# duplikasi_PCB.net
KiCad netlist of a schematic drawn in EAGLE
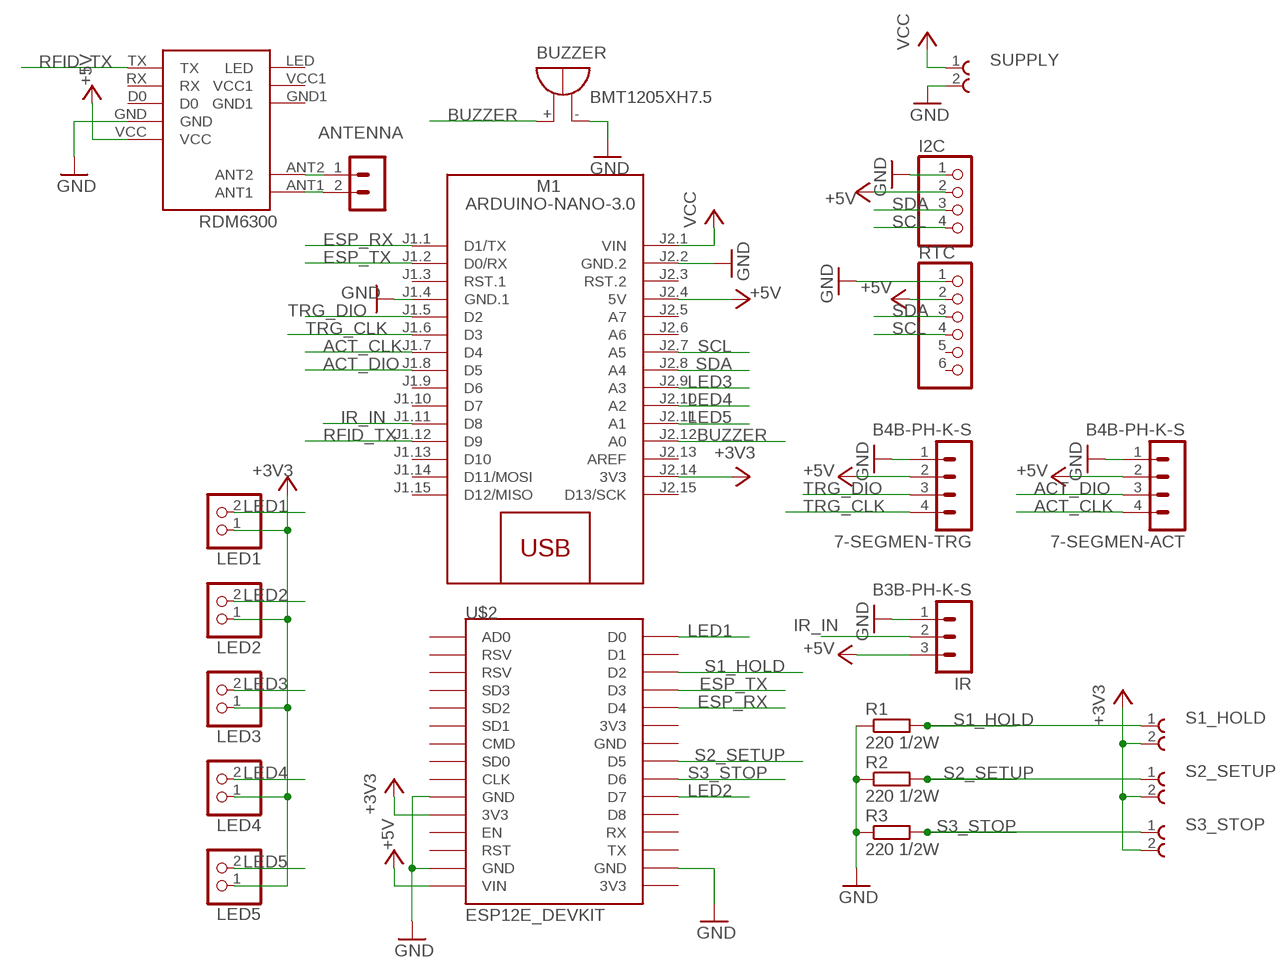
[diagram p0: schematic, sheet 1]

(export (version "E")
  (design (tool "Eeschema 10.0.6"))
  (components
    (comp (ref "7-SEGMEN-ACT")
      (value "B4B-PH-K-S")
      (footprint "eagle-import:B4B-PH-K-S")
      (libsource (lib "eagle-import") (part "B4B-PH-K-S"))
    )
    (comp (ref "7-SEGMEN-TRG")
      (value "B4B-PH-K-S")
      (footprint "eagle-import:B4B-PH-K-S")
      (libsource (lib "eagle-import") (part "B4B-PH-K-S"))
    )
    (comp (ref "ANTENNA")
      (value "B2B-PH-K-S")
      (footprint "eagle-import:B2B-PH-K-S")
      (libsource (lib "eagle-import") (part "B2B-PH-K-S"))
    )
    (comp (ref "BUZZER")
      (value "BMT1205XH7.5")
      (footprint "eagle-import:BMT1205XH7.5")
      (libsource (lib "eagle-import") (part "BMT1205XH7.5"))
    )
    (comp (ref "I2C")
      (value "PINHD-1X4")
      (footprint "eagle-import:1X04")
      (libsource (lib "eagle-import") (part "PINHD-1X4"))
    )
    (comp (ref "IR")
      (value "B3B-PH-K-S")
      (footprint "eagle-import:B3B-PH-K-S")
      (libsource (lib "eagle-import") (part "B3B-PH-K-S"))
    )
    (comp (ref "LED1")
      (value "PINHD-1X2")
      (footprint "eagle-import:1X02")
      (libsource (lib "eagle-import") (part "PINHD-1X2"))
    )
    (comp (ref "LED2")
      (value "PINHD-1X2")
      (footprint "eagle-import:1X02")
      (libsource (lib "eagle-import") (part "PINHD-1X2"))
    )
    (comp (ref "LED3")
      (value "PINHD-1X2")
      (footprint "eagle-import:1X02")
      (libsource (lib "eagle-import") (part "PINHD-1X2"))
    )
    (comp (ref "LED4")
      (value "PINHD-1X2")
      (footprint "eagle-import:1X02")
      (libsource (lib "eagle-import") (part "PINHD-1X2"))
    )
    (comp (ref "LED5")
      (value "PINHD-1X2")
      (footprint "eagle-import:1X02")
      (libsource (lib "eagle-import") (part "PINHD-1X2"))
    )
    (comp (ref "M1")
      (value "ARDUINO-NANO-3.0")
      (footprint "eagle-import:ARDUINO-NANO-3.0")
      (libsource (lib "eagle-import") (part "ARDUINO-NANO-3.0"))
    )
    (comp (ref "R1")
      (value "220 1/2W")
      (footprint "eagle-import:0207_10")
      (libsource (lib "eagle-import") (part "R-EU_0207/10"))
    )
    (comp (ref "R2")
      (value "220 1/2W")
      (footprint "eagle-import:0207_10")
      (libsource (lib "eagle-import") (part "R-EU_0207/10"))
    )
    (comp (ref "R3")
      (value "220 1/2W")
      (footprint "eagle-import:0207_10")
      (libsource (lib "eagle-import") (part "R-EU_0207/10"))
    )
    (comp (ref "RDM1")
      (value "RDM6300")
      (footprint "eagle-import:RDM6300")
      (libsource (lib "eagle-import") (part "RDM6300"))
    )
    (comp (ref "RTC")
      (value "PINHD-1X6")
      (footprint "eagle-import:1X06")
      (libsource (lib "eagle-import") (part "PINHD-1X6"))
    )
    (comp (ref "S1_HOLD")
      (value "691101710002")
      (footprint "eagle-import:691101710002")
      (libsource (lib "eagle-import") (part "691101710002"))
    )
    (comp (ref "S2_SETUP")
      (value "691101710002")
      (footprint "eagle-import:691101710002")
      (libsource (lib "eagle-import") (part "691101710002"))
    )
    (comp (ref "S3_STOP")
      (value "691101710002")
      (footprint "eagle-import:691101710002")
      (libsource (lib "eagle-import") (part "691101710002"))
    )
    (comp (ref "SUPPLY")
      (value "691101710002")
      (footprint "eagle-import:691101710002")
      (libsource (lib "eagle-import") (part "691101710002"))
    )
    (comp (ref "U$2")
      (value "ESP12E_DEVKIT")
      (footprint "eagle-import:ESP12E_DEVKIT")
      (libsource (lib "eagle-import") (part "ESP12E_DEVKIT"))
    )
  )
  (nets
    (net (code "1") (name "+3V3") (class "Default")
      (node (ref "LED1") (pin "1") (pinfunction "1_1") (pintype "passive"))
      (node (ref "LED2") (pin "1") (pinfunction "1_1") (pintype "passive"))
      (node (ref "LED3") (pin "1") (pinfunction "1_1") (pintype "passive"))
      (node (ref "LED4") (pin "1") (pinfunction "1_1") (pintype "passive"))
      (node (ref "LED5") (pin "1") (pinfunction "1_1") (pintype "passive"))
      (node (ref "M1") (pin "J2.14") (pinfunction "3V3_J2.14") (pintype "power_in"))
      (node (ref "S1_HOLD") (pin "2") (pinfunction "2_2") (pintype "passive"))
      (node (ref "S2_SETUP") (pin "2") (pinfunction "2_2") (pintype "passive"))
      (node (ref "S3_STOP") (pin "2") (pinfunction "2_2") (pintype "passive"))
      (node (ref "U$2") (pin "3V3@0") (pinfunction "3V3_3V3@0") (pintype "bidirectional"))
    )
    (net (code "2") (name "+5V") (class "Default")
      (node (ref "7-SEGMEN-ACT") (pin "2") (pinfunction "2_2") (pintype "passive"))
      (node (ref "7-SEGMEN-TRG") (pin "2") (pinfunction "2_2") (pintype "passive"))
      (node (ref "I2C") (pin "2") (pinfunction "2_2") (pintype "passive"))
      (node (ref "IR") (pin "3") (pinfunction "3_3") (pintype "passive"))
      (node (ref "M1") (pin "J2.4") (pinfunction "5V_J2.4") (pintype "power_in"))
      (node (ref "RDM1") (pin "VCC") (pinfunction "VCC_VCC") (pintype "bidirectional"))
      (node (ref "RTC") (pin "2") (pinfunction "2_2") (pintype "passive"))
      (node (ref "U$2") (pin "VIN") (pinfunction "VIN_VIN") (pintype "bidirectional"))
    )
    (net (code "3") (name "/ACT_CLK") (class "Default")
      (node (ref "7-SEGMEN-ACT") (pin "4") (pinfunction "4_4") (pintype "passive"))
      (node (ref "M1") (pin "J1.7") (pinfunction "D4_J1.7") (pintype "bidirectional"))
    )
    (net (code "4") (name "/ACT_DIO") (class "Default")
      (node (ref "7-SEGMEN-ACT") (pin "3") (pinfunction "3_3") (pintype "passive"))
      (node (ref "M1") (pin "J1.8") (pinfunction "D5_J1.8") (pintype "bidirectional"))
    )
    (net (code "5") (name "/BUZZER") (class "Default")
      (node (ref "BUZZER") (pin "+") (pinfunction "+_+") (pintype "passive"))
      (node (ref "M1") (pin "J2.12") (pinfunction "A0_J2.12") (pintype "bidirectional"))
    )
    (net (code "6") (name "/ESP_RX") (class "Default")
      (node (ref "M1") (pin "J1.1") (pinfunction "D1/TX_J1.1") (pintype "bidirectional"))
      (node (ref "U$2") (pin "D4") (pinfunction "D4_D4") (pintype "bidirectional"))
    )
    (net (code "7") (name "/ESP_TX") (class "Default")
      (node (ref "M1") (pin "J1.2") (pinfunction "D0/RX_J1.2") (pintype "bidirectional"))
      (node (ref "U$2") (pin "D3") (pinfunction "D3_D3") (pintype "bidirectional"))
    )
    (net (code "8") (name "/IR_IN") (class "Default")
      (node (ref "IR") (pin "2") (pinfunction "2_2") (pintype "passive"))
      (node (ref "M1") (pin "J1.11") (pinfunction "D8_J1.11") (pintype "bidirectional"))
    )
    (net (code "9") (name "/LED1") (class "Default")
      (node (ref "LED1") (pin "2") (pinfunction "2_2") (pintype "passive"))
      (node (ref "U$2") (pin "D0") (pinfunction "D0_D0") (pintype "bidirectional"))
    )
    (net (code "10") (name "/LED2") (class "Default")
      (node (ref "LED2") (pin "2") (pinfunction "2_2") (pintype "passive"))
      (node (ref "U$2") (pin "D7") (pinfunction "D7_D7") (pintype "bidirectional"))
    )
    (net (code "11") (name "/LED3") (class "Default")
      (node (ref "LED3") (pin "2") (pinfunction "2_2") (pintype "passive"))
      (node (ref "M1") (pin "J2.9") (pinfunction "A3_J2.9") (pintype "bidirectional"))
    )
    (net (code "12") (name "/LED4") (class "Default")
      (node (ref "LED4") (pin "2") (pinfunction "2_2") (pintype "passive"))
      (node (ref "M1") (pin "J2.10") (pinfunction "A2_J2.10") (pintype "bidirectional"))
    )
    (net (code "13") (name "/LED5") (class "Default")
      (node (ref "LED5") (pin "2") (pinfunction "2_2") (pintype "passive"))
      (node (ref "M1") (pin "J2.11") (pinfunction "A1_J2.11") (pintype "bidirectional"))
    )
    (net (code "14") (name "/RFID_TX") (class "Default")
      (node (ref "M1") (pin "J1.12") (pinfunction "D9_J1.12") (pintype "bidirectional"))
      (node (ref "RDM1") (pin "TX") (pinfunction "TX_TX") (pintype "bidirectional"))
    )
    (net (code "15") (name "/S1_HOLD") (class "Default")
      (node (ref "R1") (pin "2") (pinfunction "2_2") (pintype "passive"))
      (node (ref "S1_HOLD") (pin "1") (pinfunction "1_1") (pintype "passive"))
      (node (ref "U$2") (pin "D2") (pinfunction "D2_D2") (pintype "bidirectional"))
    )
    (net (code "16") (name "/S2_SETUP") (class "Default")
      (node (ref "R2") (pin "2") (pinfunction "2_2") (pintype "passive"))
      (node (ref "S2_SETUP") (pin "1") (pinfunction "1_1") (pintype "passive"))
      (node (ref "U$2") (pin "D5") (pinfunction "D5_D5") (pintype "bidirectional"))
    )
    (net (code "17") (name "/S3_STOP") (class "Default")
      (node (ref "R3") (pin "2") (pinfunction "2_2") (pintype "passive"))
      (node (ref "S3_STOP") (pin "1") (pinfunction "1_1") (pintype "passive"))
      (node (ref "U$2") (pin "D6") (pinfunction "D6_D6") (pintype "bidirectional"))
    )
    (net (code "18") (name "/SCL") (class "Default")
      (node (ref "I2C") (pin "4") (pinfunction "4_4") (pintype "passive"))
      (node (ref "M1") (pin "J2.7") (pinfunction "A5_J2.7") (pintype "bidirectional"))
      (node (ref "RTC") (pin "4") (pinfunction "4_4") (pintype "passive"))
    )
    (net (code "19") (name "/SDA") (class "Default")
      (node (ref "I2C") (pin "3") (pinfunction "3_3") (pintype "passive"))
      (node (ref "M1") (pin "J2.8") (pinfunction "A4_J2.8") (pintype "bidirectional"))
      (node (ref "RTC") (pin "3") (pinfunction "3_3") (pintype "passive"))
    )
    (net (code "20") (name "/TRG_CLK") (class "Default")
      (node (ref "7-SEGMEN-TRG") (pin "4") (pinfunction "4_4") (pintype "passive"))
      (node (ref "M1") (pin "J1.6") (pinfunction "D3_J1.6") (pintype "bidirectional"))
    )
    (net (code "21") (name "/TRG_DIO") (class "Default")
      (node (ref "7-SEGMEN-TRG") (pin "3") (pinfunction "3_3") (pintype "passive"))
      (node (ref "M1") (pin "J1.5") (pinfunction "D2_J1.5") (pintype "bidirectional"))
    )
    (net (code "22") (name "GND") (class "Default")
      (node (ref "7-SEGMEN-ACT") (pin "1") (pinfunction "1_1") (pintype "passive"))
      (node (ref "7-SEGMEN-TRG") (pin "1") (pinfunction "1_1") (pintype "passive"))
      (node (ref "BUZZER") (pin "-") (pinfunction "-_-") (pintype "passive"))
      (node (ref "I2C") (pin "1") (pinfunction "1_1") (pintype "passive"))
      (node (ref "IR") (pin "1") (pinfunction "1_1") (pintype "passive"))
      (node (ref "M1") (pin "J1.4") (pinfunction "GND.1_J1.4") (pintype "power_in"))
      (node (ref "M1") (pin "J2.2") (pinfunction "GND.2_J2.2") (pintype "power_in"))
      (node (ref "R1") (pin "1") (pinfunction "1_1") (pintype "passive"))
      (node (ref "R2") (pin "1") (pinfunction "1_1") (pintype "passive"))
      (node (ref "R3") (pin "1") (pinfunction "1_1") (pintype "passive"))
      (node (ref "RDM1") (pin "GND") (pinfunction "GND_GND") (pintype "bidirectional"))
      (node (ref "RTC") (pin "1") (pinfunction "1_1") (pintype "passive"))
      (node (ref "SUPPLY") (pin "2") (pinfunction "2_2") (pintype "passive"))
      (node (ref "U$2") (pin "GND@0") (pinfunction "GND_GND@0") (pintype "bidirectional"))
      (node (ref "U$2") (pin "GND@1") (pinfunction "GND_GND@1") (pintype "bidirectional"))
      (node (ref "U$2") (pin "GND@3") (pinfunction "GND_GND@3") (pintype "bidirectional"))
    )
    (net (code "23") (name "Net-(ANTENNA-Pad1)") (class "Default")
      (node (ref "ANTENNA") (pin "1") (pinfunction "1_1") (pintype "passive"))
      (node (ref "RDM1") (pin "ANT2") (pinfunction "ANT2_ANT2") (pintype "bidirectional"))
    )
    (net (code "24") (name "Net-(ANTENNA-Pad2)") (class "Default")
      (node (ref "ANTENNA") (pin "2") (pinfunction "2_2") (pintype "passive"))
      (node (ref "RDM1") (pin "ANT1") (pinfunction "ANT1_ANT1") (pintype "bidirectional"))
    )
    (net (code "25") (name "VCC") (class "Default")
      (node (ref "M1") (pin "J2.1") (pinfunction "VIN_J2.1") (pintype "power_in"))
      (node (ref "SUPPLY") (pin "1") (pinfunction "1_1") (pintype "passive"))
    )
    (net (code "26") (name "unconnected-(M1-A6-PadJ2.6)") (class "Default")
      (node (ref "M1") (pin "J2.6") (pinfunction "A6_J2.6") (pintype "bidirectional"))
    )
    (net (code "27") (name "unconnected-(M1-A7-PadJ2.5)") (class "Default")
      (node (ref "M1") (pin "J2.5") (pinfunction "A7_J2.5") (pintype "bidirectional"))
    )
    (net (code "28") (name "unconnected-(M1-AREF-PadJ2.13)") (class "Default")
      (node (ref "M1") (pin "J2.13") (pinfunction "AREF_J2.13") (pintype "bidirectional"))
    )
    (net (code "29") (name "unconnected-(M1-D6-PadJ1.9)") (class "Default")
      (node (ref "M1") (pin "J1.9") (pinfunction "D6_J1.9") (pintype "bidirectional"))
    )
    (net (code "30") (name "unconnected-(M1-D7-PadJ1.10)") (class "Default")
      (node (ref "M1") (pin "J1.10") (pinfunction "D7_J1.10") (pintype "bidirectional"))
    )
    (net (code "31") (name "unconnected-(M1-D10-PadJ1.13)") (class "Default")
      (node (ref "M1") (pin "J1.13") (pinfunction "D10_J1.13") (pintype "bidirectional"))
    )
    (net (code "32") (name "unconnected-(M1-D11{slash}MOSI-PadJ1.14)") (class "Default")
      (node (ref "M1") (pin "J1.14") (pinfunction "D11/MOSI_J1.14") (pintype "bidirectional"))
    )
    (net (code "33") (name "unconnected-(M1-D12{slash}MISO-PadJ1.15)") (class "Default")
      (node (ref "M1") (pin "J1.15") (pinfunction "D12/MISO_J1.15") (pintype "bidirectional"))
    )
    (net (code "34") (name "unconnected-(M1-D13{slash}SCK-PadJ2.15)") (class "Default")
      (node (ref "M1") (pin "J2.15") (pinfunction "D13/SCK_J2.15") (pintype "bidirectional"))
    )
    (net (code "35") (name "unconnected-(M1-RST.1-PadJ1.3)") (class "Default")
      (node (ref "M1") (pin "J1.3") (pinfunction "RST.1_J1.3") (pintype "bidirectional"))
    )
    (net (code "36") (name "unconnected-(M1-RST.2-PadJ2.3)") (class "Default")
      (node (ref "M1") (pin "J2.3") (pinfunction "RST.2_J2.3") (pintype "bidirectional"))
    )
    (net (code "37") (name "unconnected-(RDM1-PadD0)") (class "Default")
      (node (ref "RDM1") (pin "D0") (pinfunction "D0_D0") (pintype "bidirectional"))
    )
    (net (code "38") (name "unconnected-(RDM1-PadGND1)") (class "Default")
      (node (ref "RDM1") (pin "GND1") (pinfunction "GND1_GND1") (pintype "bidirectional"))
    )
    (net (code "39") (name "unconnected-(RDM1-PadLED)") (class "Default")
      (node (ref "RDM1") (pin "LED") (pinfunction "LED_LED") (pintype "bidirectional"))
    )
    (net (code "40") (name "unconnected-(RDM1-PadRX)") (class "Default")
      (node (ref "RDM1") (pin "RX") (pinfunction "RX_RX") (pintype "bidirectional"))
    )
    (net (code "41") (name "unconnected-(RDM1-PadVCC1)") (class "Default")
      (node (ref "RDM1") (pin "VCC1") (pinfunction "VCC1_VCC1") (pintype "bidirectional"))
    )
    (net (code "42") (name "unconnected-(RTC-Pad5)") (class "Default")
      (node (ref "RTC") (pin "5") (pinfunction "5_5") (pintype "passive"))
    )
    (net (code "43") (name "unconnected-(RTC-Pad6)") (class "Default")
      (node (ref "RTC") (pin "6") (pinfunction "6_6") (pintype "passive"))
    )
    (net (code "44") (name "unconnected-(U$2-3V3-Pad3V3@1)") (class "Default")
      (node (ref "U$2") (pin "3V3@1") (pinfunction "3V3_3V3@1") (pintype "bidirectional"))
    )
    (net (code "45") (name "unconnected-(U$2-3V3-Pad3V3@2)") (class "Default")
      (node (ref "U$2") (pin "3V3@2") (pinfunction "3V3_3V3@2") (pintype "bidirectional"))
    )
    (net (code "46") (name "unconnected-(U$2-GND-PadGND@2)") (class "Default")
      (node (ref "U$2") (pin "GND@2") (pinfunction "GND_GND@2") (pintype "bidirectional"))
    )
    (net (code "47") (name "unconnected-(U$2-PadAD0)") (class "Default")
      (node (ref "U$2") (pin "AD0") (pinfunction "AD0_AD0") (pintype "bidirectional"))
    )
    (net (code "48") (name "unconnected-(U$2-PadCLK)") (class "Default")
      (node (ref "U$2") (pin "CLK") (pinfunction "CLK_CLK") (pintype "bidirectional"))
    )
    (net (code "49") (name "unconnected-(U$2-PadCMD)") (class "Default")
      (node (ref "U$2") (pin "CMD") (pinfunction "CMD_CMD") (pintype "bidirectional"))
    )
    (net (code "50") (name "unconnected-(U$2-PadD1)") (class "Default")
      (node (ref "U$2") (pin "D1") (pinfunction "D1_D1") (pintype "bidirectional"))
    )
    (net (code "51") (name "unconnected-(U$2-PadD8)") (class "Default")
      (node (ref "U$2") (pin "D8") (pinfunction "D8_D8") (pintype "bidirectional"))
    )
    (net (code "52") (name "unconnected-(U$2-PadEN)") (class "Default")
      (node (ref "U$2") (pin "EN") (pinfunction "EN_EN") (pintype "bidirectional"))
    )
    (net (code "53") (name "unconnected-(U$2-PadRST)") (class "Default")
      (node (ref "U$2") (pin "RST") (pinfunction "RST_RST") (pintype "bidirectional"))
    )
    (net (code "54") (name "unconnected-(U$2-PadRX)") (class "Default")
      (node (ref "U$2") (pin "RX") (pinfunction "RX_RX") (pintype "bidirectional"))
    )
    (net (code "55") (name "unconnected-(U$2-PadSD0)") (class "Default")
      (node (ref "U$2") (pin "SD0") (pinfunction "SD0_SD0") (pintype "bidirectional"))
    )
    (net (code "56") (name "unconnected-(U$2-PadSD1)") (class "Default")
      (node (ref "U$2") (pin "SD1") (pinfunction "SD1_SD1") (pintype "bidirectional"))
    )
    (net (code "57") (name "unconnected-(U$2-PadSD2)") (class "Default")
      (node (ref "U$2") (pin "SD2") (pinfunction "SD2_SD2") (pintype "bidirectional"))
    )
    (net (code "58") (name "unconnected-(U$2-PadSD3)") (class "Default")
      (node (ref "U$2") (pin "SD3") (pinfunction "SD3_SD3") (pintype "bidirectional"))
    )
    (net (code "59") (name "unconnected-(U$2-PadTX)") (class "Default")
      (node (ref "U$2") (pin "TX") (pinfunction "TX_TX") (pintype "bidirectional"))
    )
    (net (code "60") (name "unconnected-(U$2-RSV-PadRSV@0)") (class "Default")
      (node (ref "U$2") (pin "RSV@0") (pinfunction "RSV_RSV@0") (pintype "bidirectional"))
    )
    (net (code "61") (name "unconnected-(U$2-RSV-PadRSV@1)") (class "Default")
      (node (ref "U$2") (pin "RSV@1") (pinfunction "RSV_RSV@1") (pintype "bidirectional"))
    )
  )
)
